# 5V_Buck.net
KiCad netlist of a schematic drawn in Altium Designer
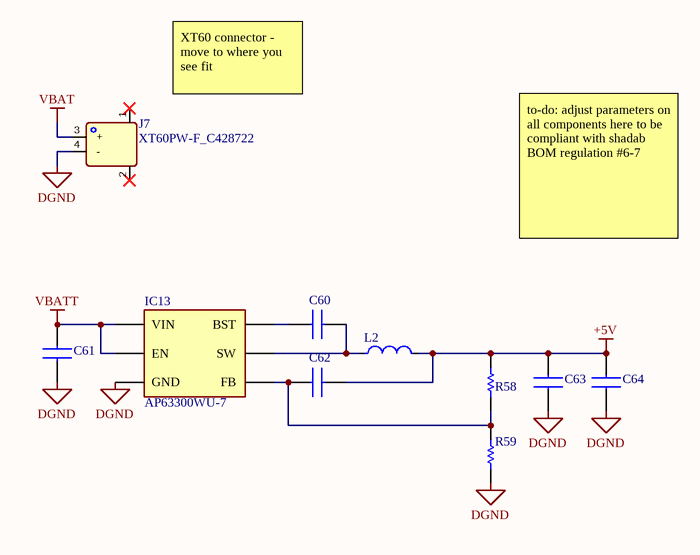
[diagram p0: +5V_Buck.SchDoc]

(export (version "E")
  (design (tool "Eeschema 10.0.6"))
  (components
    (comp (ref "C60")
      (value "0603,X7R,100nF,50V,10%")
      (footprint "CAPC1608X90N")
      (description "50V 100nF X7R ±10% 0603 Multilayer Ceramic Capacitors MLCC - SMD/SMT ROHS")
      (fields (field (name "LCSC PART #") "C14663") (field (name "MANU PART #") "CC0603KRX7R9BB104"))
      (libsource (lib "flight-controller") (part "CC0603KRX7R9BB104"))
    )
    (comp (ref "C61")
      (value "0805,X7R,10uF,25V,10%")
      (footprint "CAPC2012X145N")
      (description "10uF ±10% 25V Ceramic Capacitor X7R 0805")
      (fields (field (name "LCSC PART #") "C3039694") (field (name "MANU PART #") "CL21B106KAYQNNE"))
      (libsource (lib "flight-controller") (part "CL21B106KAYQNNE"))
    )
    (comp (ref "C62")
      (value "0603,NP0,47pF,50V,5%")
      (footprint "CAPC1608X90N")
      (description "47 pF ±5% 50V Ceramic Capacitor C0G, NP0 0603 (1608 Metric)")
      (fields (field (name "MANU PART #") "CC0603JRNPO9BN470") (field (name "LCSC PART #") "C105622"))
      (libsource (lib "flight-controller") (part "CC0603JRNPO9BN470"))
    )
    (comp (ref "C63")
      (value "0805,X5R,22uF,25V,20%")
      (footprint "CAPC2012X145N")
      (description "22uF ±20% 25V Ceramic Capacitor X5R 0805")
      (fields (field (name "LCSC PART #") "C602037") (field (name "MANU PART #") "CL21A226MAYNNNE"))
      (libsource (lib "flight-controller") (part "CL21A226MAYNNNE"))
    )
    (comp (ref "C64")
      (value "0805,X5R,22uF,25V,20%")
      (footprint "CAPC2012X145N")
      (description "22uF ±20% 25V Ceramic Capacitor X5R 0805")
      (fields (field (name "LCSC PART #") "C602037") (field (name "MANU PART #") "CL21A226MAYNNNE"))
      (libsource (lib "flight-controller") (part "CL21A226MAYNNNE"))
    )
    (comp (ref "IC13")
      (value "AP63300WU-7")
      (footprint "SOT95P280X90-6N")
      (description "Integrated Circuit")
      (fields (field (name "MOUSER PART NUMBER") "621-AP63300WU-7"))
      (libsource (lib "flight-controller") (part "AP63300WU-7"))
    )
    (comp (ref "J7")
      (value "XT60PW-F_C428722")
      (footprint "XT60PW-F_C428722")
      (description "Horizontal plug Yellow - Power connector / plug connector")
      (fields (field (name "LCSC PART #") "C428722") (field (name "MANU PART #") "XT60PW-F"))
      (libsource (lib "flight-controller") (part "XT60PW-F_C428722"))
    )
    (comp (ref "L2")
      (value "FXL0630-6R8-M")
      (footprint "FXL0630-6R8-M")
      (description "48mΩ 5A 6.8uH 6A Molded Inductor ±20% SMD,7x6.6mm Power Inductors ROHS")
      (fields (field (name "MANUFACTURER") "cjiang (Changjiang Microelectronics Tech)"))
      (libsource (lib "flight-controller") (part "FXL0630-6R8-M"))
    )
    (comp (ref "R58")
      (value "FRC0603F1583TS")
      (footprint "FRC0603F1583TS")
      (fields (field (name "MANUFACTURER") "FOJAN"))
      (libsource (lib "flight-controller") (part "FRC0603F1583TS"))
    )
    (comp (ref "R59")
      (value "RC0603FR-0730K1L")
      (footprint "RC0603FR-0730K1L")
      (fields (field (name "MANUFACTURER") "YAGEO"))
      (libsource (lib "flight-controller") (part "RC0603FR-0730K1L"))
    )
  )
  (nets
    (net (code "1") (name "+5V") (class "Default")
      (node (ref "C62") (pin "1") (pinfunction "1_1") (pintype "passive"))
      (node (ref "C63") (pin "2") (pinfunction "2_2") (pintype "passive"))
      (node (ref "C64") (pin "2") (pinfunction "2_2") (pintype "passive"))
      (node (ref "L2") (pin "2") (pinfunction "2_2") (pintype "passive"))
      (node (ref "R58") (pin "2") (pinfunction "2_2") (pintype "passive"))
    )
    (net (code "2") (name "DGND") (class "Default")
      (node (ref "C61") (pin "2") (pinfunction "2_2") (pintype "passive"))
      (node (ref "C63") (pin "1") (pinfunction "1_1") (pintype "passive"))
      (node (ref "C64") (pin "1") (pinfunction "1_1") (pintype "passive"))
      (node (ref "IC13") (pin "4") (pinfunction "GND_4") (pintype "passive"))
      (node (ref "J7") (pin "4") (pinfunction "-_4") (pintype "passive"))
      (node (ref "R59") (pin "1") (pinfunction "1_1") (pintype "passive"))
    )
    (net (code "3") (name "Net-(IC13-BST)") (class "Default")
      (node (ref "C60") (pin "1") (pinfunction "1_1") (pintype "passive"))
      (node (ref "IC13") (pin "6") (pinfunction "BST_6") (pintype "passive"))
    )
    (net (code "4") (name "Net-(IC13-FB)") (class "Default")
      (node (ref "C62") (pin "2") (pinfunction "2_2") (pintype "passive"))
      (node (ref "IC13") (pin "1") (pinfunction "FB_1") (pintype "passive"))
      (node (ref "R58") (pin "1") (pinfunction "1_1") (pintype "passive"))
      (node (ref "R59") (pin "2") (pinfunction "2_2") (pintype "passive"))
    )
    (net (code "5") (name "Net-(IC13-SW)") (class "Default")
      (node (ref "C60") (pin "2") (pinfunction "2_2") (pintype "passive"))
      (node (ref "IC13") (pin "5") (pinfunction "SW_5") (pintype "passive"))
      (node (ref "L2") (pin "1") (pinfunction "1_1") (pintype "passive"))
    )
    (net (code "6") (name "VBAT") (class "Default")
      (node (ref "J7") (pin "3") (pinfunction "+_3") (pintype "passive"))
    )
    (net (code "7") (name "VBATT") (class "Default")
      (node (ref "C61") (pin "1") (pinfunction "1_1") (pintype "passive"))
      (node (ref "IC13") (pin "2") (pinfunction "EN_2") (pintype "passive"))
      (node (ref "IC13") (pin "3") (pinfunction "VIN_3") (pintype "passive"))
    )
    (net (code "8") (name "unconnected-(J7-Pad1)") (class "Default")
      (node (ref "J7") (pin "1") (pinfunction "1_1") (pintype "passive+no_connect"))
    )
    (net (code "9") (name "unconnected-(J7-Pad2)") (class "Default")
      (node (ref "J7") (pin "2") (pinfunction "2_2") (pintype "passive+no_connect"))
    )
  )
)
